# final_2_connectors.net
KiCad netlist of a schematic drawn in EAGLE
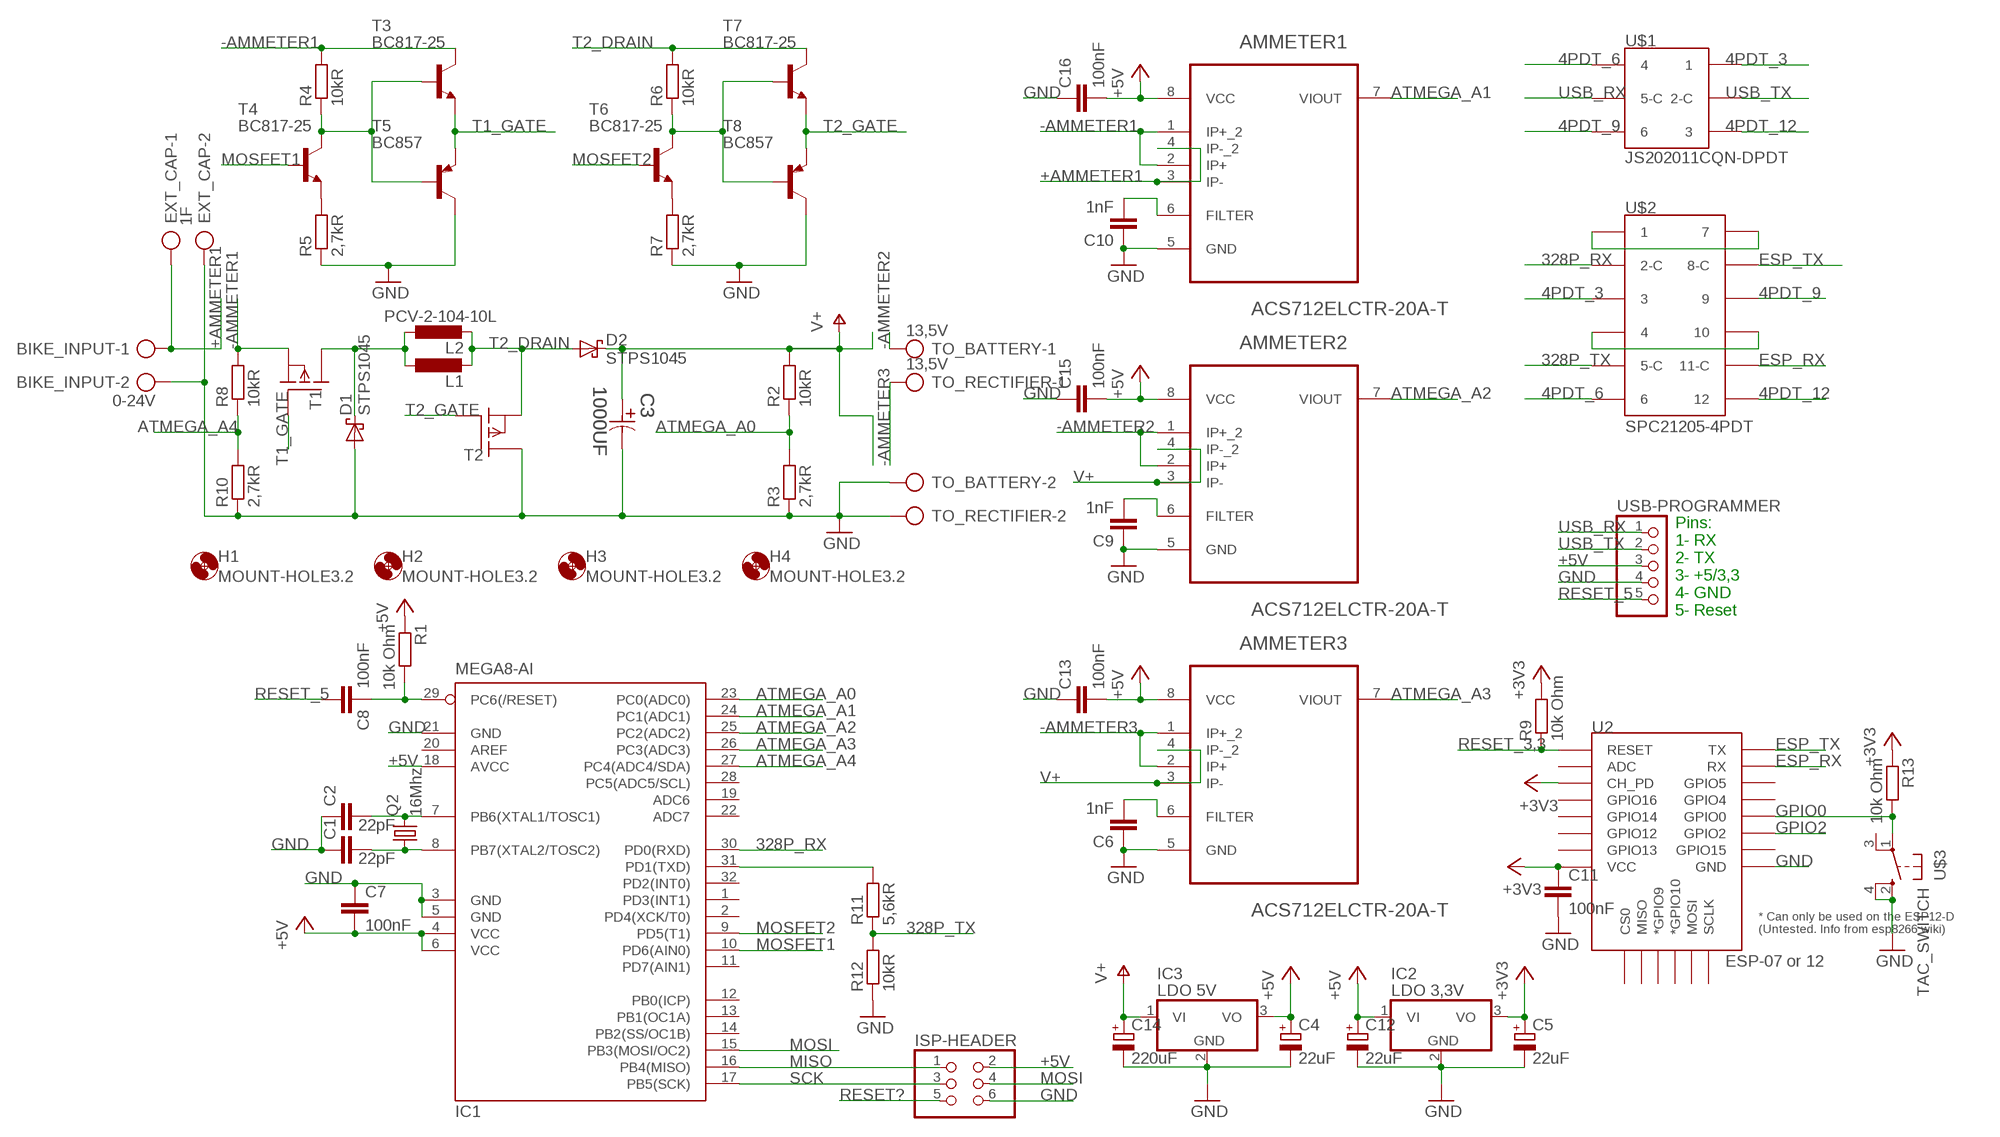
[diagram p0: schematic, sheet 1]

(export (version "E")
  (design (tool "Eeschema 10.0.6"))
  (components
    (comp (ref "AMMETER1")
      (value "ACS712ELCTR-20A-T")
      (footprint "eagle-import:SOIC127P600X175-8N")
      (libsource (lib "eagle-import") (part "ACS712ELCTR-20A-T"))
    )
    (comp (ref "AMMETER2")
      (value "ACS712ELCTR-20A-T")
      (footprint "eagle-import:SOIC127P600X175-8N")
      (libsource (lib "eagle-import") (part "ACS712ELCTR-20A-T"))
    )
    (comp (ref "AMMETER3")
      (value "ACS712ELCTR-20A-T")
      (footprint "eagle-import:SOIC127P600X175-8N")
      (libsource (lib "eagle-import") (part "ACS712ELCTR-20A-T"))
    )
    (comp (ref "BIKE_INPUT")
      (value "0-24V")
      (footprint "eagle-import:AK500_2")
      (libsource (lib "eagle-import") (part "AK500/2"))
    )
    (comp (ref "C1")
      (value "22pF")
      (footprint "eagle-import:C0805")
      (libsource (lib "eagle-import") (part "C-EUC0805"))
    )
    (comp (ref "C2")
      (value "22pF")
      (footprint "eagle-import:C0805")
      (libsource (lib "eagle-import") (part "C-EUC0805"))
    )
    (comp (ref "C3")
      (value "1000UF")
      (footprint "eagle-import:CAPAE1700X1700N")
      (fields (field (name "MPN") "EEVFK1H102M") (field (name "TOLERANCE") "±20 %"))
      (libsource (lib "eagle-import") (part "EEV--CASE-J16FK1H102M"))
    )
    (comp (ref "C4")
      (value "22uF")
      (footprint "eagle-import:153CLV-0505")
      (libsource (lib "eagle-import") (part "CPOL-EU153CLV-0505"))
    )
    (comp (ref "C5")
      (value "22uF")
      (footprint "eagle-import:153CLV-0505")
      (libsource (lib "eagle-import") (part "CPOL-EU153CLV-0505"))
    )
    (comp (ref "C6")
      (value "1nF")
      (footprint "eagle-import:C0805")
      (libsource (lib "eagle-import") (part "C-EUC0805"))
    )
    (comp (ref "C7")
      (value "100nF")
      (footprint "eagle-import:C0805")
      (libsource (lib "eagle-import") (part "C-EUC0805"))
    )
    (comp (ref "C8")
      (value "100nF")
      (footprint "eagle-import:C0805")
      (libsource (lib "eagle-import") (part "C-EUC0805"))
    )
    (comp (ref "C9")
      (value "1nF")
      (footprint "eagle-import:C0805")
      (libsource (lib "eagle-import") (part "C-EUC0805"))
    )
    (comp (ref "C10")
      (value "1nF")
      (footprint "eagle-import:C0805")
      (libsource (lib "eagle-import") (part "C-EUC0805"))
    )
    (comp (ref "C11")
      (value "100nF")
      (footprint "eagle-import:C0805")
      (libsource (lib "eagle-import") (part "C-EUC0805"))
    )
    (comp (ref "C12")
      (value "22uF")
      (footprint "eagle-import:153CLV-0505")
      (libsource (lib "eagle-import") (part "CPOL-EU153CLV-0505"))
    )
    (comp (ref "C13")
      (value "100nF")
      (footprint "eagle-import:C0805")
      (libsource (lib "eagle-import") (part "C-EUC0805"))
    )
    (comp (ref "C14")
      (value "220uF")
      (footprint "eagle-import:153CLV-0807")
      (libsource (lib "eagle-import") (part "CPOL-EU153CLV-0807"))
    )
    (comp (ref "C15")
      (value "100nF")
      (footprint "eagle-import:C0805")
      (libsource (lib "eagle-import") (part "C-EUC0805"))
    )
    (comp (ref "C16")
      (value "100nF")
      (footprint "eagle-import:C0805")
      (libsource (lib "eagle-import") (part "C-EUC0805"))
    )
    (comp (ref "D1")
      (value "STPS1045")
      (footprint "eagle-import:TO220AC")
      (libsource (lib "eagle-import") (part "STPS1045"))
    )
    (comp (ref "D2")
      (value "STPS1045")
      (footprint "eagle-import:TO220AC")
      (libsource (lib "eagle-import") (part "STPS1045"))
    )
    (comp (ref "EXT_CAP")
      (value "1F")
      (footprint "eagle-import:AK500_2")
      (libsource (lib "eagle-import") (part "AK500/2"))
    )
    (comp (ref "H1")
      (value "MOUNT-HOLE3.2")
      (footprint "eagle-import:3,2")
      (libsource (lib "eagle-import") (part "MOUNT-HOLE3.2"))
    )
    (comp (ref "H2")
      (value "MOUNT-HOLE3.2")
      (footprint "eagle-import:3,2")
      (libsource (lib "eagle-import") (part "MOUNT-HOLE3.2"))
    )
    (comp (ref "H3")
      (value "MOUNT-HOLE3.2")
      (footprint "eagle-import:3,2")
      (libsource (lib "eagle-import") (part "MOUNT-HOLE3.2"))
    )
    (comp (ref "H4")
      (value "MOUNT-HOLE3.2")
      (footprint "eagle-import:3,2")
      (libsource (lib "eagle-import") (part "MOUNT-HOLE3.2"))
    )
    (comp (ref "IC1")
      (value "MEGA8-AI")
      (footprint "eagle-import:TQFP32-08")
      (fields (field (name "MPN") "ATMEGA8-16AU"))
      (libsource (lib "eagle-import") (part "MEGA8-AI"))
    )
    (comp (ref "IC2")
      (value "LDO 3,3V")
      (footprint "eagle-import:SOT223")
      (libsource (lib "eagle-import") (part "MCP1703DB"))
    )
    (comp (ref "IC3")
      (value "LDO 5V")
      (footprint "eagle-import:SOT223")
      (libsource (lib "eagle-import") (part "MCP1703DB"))
    )
    (comp (ref "ISP-HEADER")
      (value "PINHD-2X3")
      (footprint "eagle-import:2X03")
      (libsource (lib "eagle-import") (part "PINHD-2X3"))
    )
    (comp (ref "L1")
      (value "PCV-2-104-10L")
      (footprint "eagle-import:TJ5-U2")
      (libsource (lib "eagle-import") (part "PCV-2-104-10L"))
    )
    (comp (ref "L2")
      (value "PCV-2-104-10L")
      (footprint "eagle-import:TJ5-U2")
      (libsource (lib "eagle-import") (part "PCV-2-104-10L"))
    )
    (comp (ref "Q2")
      (value "16Mhz")
      (footprint "eagle-import:HC49UP")
      (libsource (lib "eagle-import") (part "CRYSTALHC49UP"))
    )
    (comp (ref "R1")
      (value "10k Ohm")
      (footprint "eagle-import:M0805")
      (libsource (lib "eagle-import") (part "R-EU_M0805"))
    )
    (comp (ref "R2")
      (value "10kR")
      (footprint "eagle-import:M0805")
      (libsource (lib "eagle-import") (part "R-EU_M0805"))
    )
    (comp (ref "R3")
      (value "2,7kR")
      (footprint "eagle-import:M0805")
      (libsource (lib "eagle-import") (part "R-EU_M0805"))
    )
    (comp (ref "R4")
      (value "10kR")
      (footprint "eagle-import:M0805")
      (libsource (lib "eagle-import") (part "R-EU_M0805"))
    )
    (comp (ref "R5")
      (value "2,7kR")
      (footprint "eagle-import:M0805")
      (libsource (lib "eagle-import") (part "R-EU_M0805"))
    )
    (comp (ref "R6")
      (value "10kR")
      (footprint "eagle-import:M0805")
      (libsource (lib "eagle-import") (part "R-EU_M0805"))
    )
    (comp (ref "R7")
      (value "2,7kR")
      (footprint "eagle-import:M0805")
      (libsource (lib "eagle-import") (part "R-EU_M0805"))
    )
    (comp (ref "R8")
      (value "10kR")
      (footprint "eagle-import:M0805")
      (libsource (lib "eagle-import") (part "R-EU_M0805"))
    )
    (comp (ref "R9")
      (value "10k Ohm")
      (footprint "eagle-import:M0805")
      (libsource (lib "eagle-import") (part "R-EU_M0805"))
    )
    (comp (ref "R10")
      (value "2,7kR")
      (footprint "eagle-import:M0805")
      (libsource (lib "eagle-import") (part "R-EU_M0805"))
    )
    (comp (ref "R11")
      (value "5,6kR")
      (footprint "eagle-import:M0805")
      (libsource (lib "eagle-import") (part "R-EU_M0805"))
    )
    (comp (ref "R12")
      (value "10kR")
      (footprint "eagle-import:M0805")
      (libsource (lib "eagle-import") (part "R-EU_M0805"))
    )
    (comp (ref "R13")
      (value "10k Ohm")
      (footprint "eagle-import:M0805")
      (libsource (lib "eagle-import") (part "R-EU_M0805"))
    )
    (comp (ref "T1")
      (value "SUP65P06-20")
      (footprint "eagle-import:TO220")
      (libsource (lib "eagle-import") (part "SUP65P06-20"))
    )
    (comp (ref "T2")
      (value "SUP65P06-20")
      (footprint "eagle-import:TO220")
      (libsource (lib "eagle-import") (part "SUP65P06-20"))
    )
    (comp (ref "T3")
      (value "BC817-25")
      (footprint "eagle-import:SOT23-BEC")
      (libsource (lib "eagle-import") (part "-NPN-SOT23-BECBC817-25"))
    )
    (comp (ref "T4")
      (value "BC817-25")
      (footprint "eagle-import:SOT23-BEC")
      (libsource (lib "eagle-import") (part "-NPN-SOT23-BECBC817-25"))
    )
    (comp (ref "T5")
      (value "BC857")
      (footprint "eagle-import:SOT23-BEC")
      (libsource (lib "eagle-import") (part "-PNP-SOT23-BECBC857ALT1"))
    )
    (comp (ref "T6")
      (value "BC817-25")
      (footprint "eagle-import:SOT23-BEC")
      (libsource (lib "eagle-import") (part "-NPN-SOT23-BECBC817-25"))
    )
    (comp (ref "T7")
      (value "BC817-25")
      (footprint "eagle-import:SOT23-BEC")
      (libsource (lib "eagle-import") (part "-NPN-SOT23-BECBC817-25"))
    )
    (comp (ref "T8")
      (value "BC857")
      (footprint "eagle-import:SOT23-BEC")
      (libsource (lib "eagle-import") (part "-PNP-SOT23-BECBC857ALT1"))
    )
    (comp (ref "TO_BATTERY")
      (value "13,5V")
      (footprint "eagle-import:AK500_2")
      (libsource (lib "eagle-import") (part "AK500/2"))
    )
    (comp (ref "TO_RECTIFIER")
      (value "13,5V")
      (footprint "eagle-import:AK500_2")
      (libsource (lib "eagle-import") (part "AK500/2"))
    )
    (comp (ref "U$1")
      (value "JS202011CQN-DPDT")
      (footprint "eagle-import:2X3_SWITCH")
      (libsource (lib "eagle-import") (part "JS202011CQN-DPDT"))
    )
    (comp (ref "U$2")
      (value "SPC21205-4PDT")
      (footprint "eagle-import:2X6_SWITCH")
      (libsource (lib "eagle-import") (part "SPC21205-4PDT"))
    )
    (comp (ref "U$3")
      (value "TAC_SWITCH")
      (footprint "eagle-import:TL1105SP")
      (libsource (lib "eagle-import") (part "TAC_SWITCH"))
    )
    (comp (ref "U2")
      (value "ESP-07 or 12")
      (footprint "eagle-import:ESP12E-SMD")
      (libsource (lib "eagle-import") (part "ESP12ESMD"))
    )
    (comp (ref "USB-PROGRAMMER")
      (value "PINHD-1X5")
      (footprint "eagle-import:1X05")
      (libsource (lib "eagle-import") (part "PINHD-1X5"))
    )
  )
  (nets
    (net (code "1") (name "+3V3") (class "Default")
      (node (ref "C11") (pin "1") (pinfunction "1_1") (pintype "passive"))
      (node (ref "C5") (pin "+") (pinfunction "+_+") (pintype "passive"))
      (node (ref "IC2") (pin "3") (pinfunction "VO_3") (pintype "passive"))
      (node (ref "R13") (pin "1") (pinfunction "1_1") (pintype "passive"))
      (node (ref "R9") (pin "2") (pinfunction "2_2") (pintype "passive"))
      (node (ref "U2") (pin "CH_PD") (pinfunction "CH_PD_CH_PD") (pintype "bidirectional"))
      (node (ref "U2") (pin "VCC") (pinfunction "VCC_VCC") (pintype "bidirectional"))
    )
    (net (code "2") (name "+5V") (class "Default")
      (node (ref "AMMETER1") (pin "8") (pinfunction "VCC_8") (pintype "power_in"))
      (node (ref "AMMETER2") (pin "8") (pinfunction "VCC_8") (pintype "power_in"))
      (node (ref "AMMETER3") (pin "8") (pinfunction "VCC_8") (pintype "power_in"))
      (node (ref "C12") (pin "+") (pinfunction "+_+") (pintype "passive"))
      (node (ref "C13") (pin "2") (pinfunction "2_2") (pintype "passive"))
      (node (ref "C15") (pin "2") (pinfunction "2_2") (pintype "passive"))
      (node (ref "C16") (pin "2") (pinfunction "2_2") (pintype "passive"))
      (node (ref "C4") (pin "+") (pinfunction "+_+") (pintype "passive"))
      (node (ref "C7") (pin "2") (pinfunction "2_2") (pintype "passive"))
      (node (ref "IC1") (pin "18") (pinfunction "AVCC_18") (pintype "power_in"))
      (node (ref "IC1") (pin "4") (pinfunction "VCC_4") (pintype "power_in"))
      (node (ref "IC1") (pin "6") (pinfunction "VCC_6") (pintype "power_in"))
      (node (ref "IC2") (pin "1") (pinfunction "VI_1") (pintype "input"))
      (node (ref "IC3") (pin "3") (pinfunction "VO_3") (pintype "passive"))
      (node (ref "ISP-HEADER") (pin "2") (pinfunction "2_2") (pintype "passive"))
      (node (ref "R1") (pin "1") (pinfunction "1_1") (pintype "passive"))
      (node (ref "USB-PROGRAMMER") (pin "3") (pinfunction "3_3") (pintype "passive"))
    )
    (net (code "3") (name "/+AMMETER1") (class "Default")
      (node (ref "AMMETER1") (pin "3") (pinfunction "IP-_3") (pintype "input"))
      (node (ref "AMMETER1") (pin "4") (pinfunction "IP-_2_4") (pintype "input"))
      (node (ref "BIKE_INPUT") (pin "1") (pinfunction "KL_1") (pintype "passive"))
      (node (ref "EXT_CAP") (pin "1") (pinfunction "KL_1") (pintype "passive"))
    )
    (net (code "4") (name "/-AMMETER1") (class "Default")
      (node (ref "AMMETER1") (pin "1") (pinfunction "IP+_2_1") (pintype "input"))
      (node (ref "AMMETER1") (pin "2") (pinfunction "IP+_2") (pintype "input"))
      (node (ref "R4") (pin "2") (pinfunction "2_2") (pintype "passive"))
      (node (ref "R8") (pin "2") (pinfunction "2_2") (pintype "passive"))
      (node (ref "T1") (pin "3") (pinfunction "S_3") (pintype "passive"))
      (node (ref "T3") (pin "C") (pinfunction "C_C") (pintype "passive"))
    )
    (net (code "5") (name "/-AMMETER2") (class "Default")
      (node (ref "AMMETER2") (pin "1") (pinfunction "IP+_2_1") (pintype "input"))
      (node (ref "AMMETER2") (pin "2") (pinfunction "IP+_2") (pintype "input"))
      (node (ref "TO_BATTERY") (pin "1") (pinfunction "KL_1") (pintype "passive"))
    )
    (net (code "6") (name "/-AMMETER3") (class "Default")
      (node (ref "AMMETER3") (pin "1") (pinfunction "IP+_2_1") (pintype "input"))
      (node (ref "AMMETER3") (pin "2") (pinfunction "IP+_2") (pintype "input"))
      (node (ref "TO_RECTIFIER") (pin "1") (pinfunction "KL_1") (pintype "passive"))
    )
    (net (code "7") (name "/4PDT_3") (class "Default")
      (node (ref "U$1") (pin "1") (pinfunction "1_1") (pintype "bidirectional"))
      (node (ref "U$2") (pin "3") (pinfunction "3_3") (pintype "bidirectional"))
    )
    (net (code "8") (name "/4PDT_6") (class "Default")
      (node (ref "U$1") (pin "4") (pinfunction "4_4") (pintype "bidirectional"))
      (node (ref "U$2") (pin "6") (pinfunction "6_6") (pintype "bidirectional"))
    )
    (net (code "9") (name "/4PDT_9") (class "Default")
      (node (ref "U$1") (pin "6") (pinfunction "6_6") (pintype "bidirectional"))
      (node (ref "U$2") (pin "9") (pinfunction "9_9") (pintype "bidirectional"))
    )
    (net (code "10") (name "/4PDT_12") (class "Default")
      (node (ref "U$1") (pin "3") (pinfunction "3_3") (pintype "bidirectional"))
      (node (ref "U$2") (pin "12") (pinfunction "12_12") (pintype "bidirectional"))
    )
    (net (code "11") (name "/328P_RX") (class "Default")
      (node (ref "IC1") (pin "30") (pinfunction "PD0(RXD)_30") (pintype "bidirectional"))
      (node (ref "U$2") (pin "2-C") (pinfunction "2-C_2-C") (pintype "bidirectional"))
    )
    (net (code "12") (name "/328P_TX") (class "Default")
      (node (ref "R11") (pin "1") (pinfunction "1_1") (pintype "passive"))
      (node (ref "R12") (pin "2") (pinfunction "2_2") (pintype "passive"))
      (node (ref "U$2") (pin "5-C") (pinfunction "5-C_5-C") (pintype "bidirectional"))
    )
    (net (code "13") (name "/ATMEGA_A0") (class "Default")
      (node (ref "IC1") (pin "23") (pinfunction "PC0(ADC0)_23") (pintype "bidirectional"))
      (node (ref "R2") (pin "1") (pinfunction "1_1") (pintype "passive"))
      (node (ref "R3") (pin "2") (pinfunction "2_2") (pintype "passive"))
    )
    (net (code "14") (name "/ATMEGA_A1") (class "Default")
      (node (ref "AMMETER1") (pin "7") (pinfunction "VIOUT_7") (pintype "output"))
      (node (ref "IC1") (pin "24") (pinfunction "PC1(ADC1)_24") (pintype "bidirectional"))
    )
    (net (code "15") (name "/ATMEGA_A2") (class "Default")
      (node (ref "AMMETER2") (pin "7") (pinfunction "VIOUT_7") (pintype "output"))
      (node (ref "IC1") (pin "25") (pinfunction "PC2(ADC2)_25") (pintype "bidirectional"))
    )
    (net (code "16") (name "/ATMEGA_A3") (class "Default")
      (node (ref "AMMETER3") (pin "7") (pinfunction "VIOUT_7") (pintype "output"))
      (node (ref "IC1") (pin "26") (pinfunction "PC3(ADC3)_26") (pintype "bidirectional"))
    )
    (net (code "17") (name "/ATMEGA_A4") (class "Default")
      (node (ref "IC1") (pin "27") (pinfunction "PC4(ADC4/SDA)_27") (pintype "bidirectional"))
      (node (ref "R10") (pin "2") (pinfunction "2_2") (pintype "passive"))
      (node (ref "R8") (pin "1") (pinfunction "1_1") (pintype "passive"))
    )
    (net (code "18") (name "/ESP_RX") (class "Default")
      (node (ref "U$2") (pin "11-C") (pinfunction "11-C_11-C") (pintype "bidirectional"))
      (node (ref "U2") (pin "RXD0") (pinfunction "RX_RXD0") (pintype "bidirectional"))
    )
    (net (code "19") (name "/ESP_TX") (class "Default")
      (node (ref "U$2") (pin "8-C") (pinfunction "8-C_8-C") (pintype "bidirectional"))
      (node (ref "U2") (pin "TXD0") (pinfunction "TX_TXD0") (pintype "bidirectional"))
    )
    (net (code "20") (name "/GPIO0") (class "Default")
      (node (ref "R13") (pin "2") (pinfunction "2_2") (pintype "passive"))
      (node (ref "U$3") (pin "1") (pinfunction "P_1") (pintype "passive"))
      (node (ref "U2") (pin "GPIO0") (pinfunction "GPIO0_GPIO0") (pintype "bidirectional"))
    )
    (net (code "21") (name "/GPIO2") (class "Default")
      (node (ref "U2") (pin "GPIO2") (pinfunction "GPIO2_GPIO2") (pintype "bidirectional"))
    )
    (net (code "22") (name "/MISO") (class "Default")
      (node (ref "IC1") (pin "16") (pinfunction "PB4(MISO)_16") (pintype "bidirectional"))
      (node (ref "ISP-HEADER") (pin "1") (pinfunction "1_1") (pintype "passive"))
    )
    (net (code "23") (name "/MOSFET1") (class "Default")
      (node (ref "IC1") (pin "10") (pinfunction "PD6(AIN0)_10") (pintype "bidirectional"))
      (node (ref "T4") (pin "B") (pinfunction "B_B") (pintype "passive"))
    )
    (net (code "24") (name "/MOSFET2") (class "Default")
      (node (ref "IC1") (pin "9") (pinfunction "PD5(T1)_9") (pintype "bidirectional"))
      (node (ref "T6") (pin "B") (pinfunction "B_B") (pintype "passive"))
    )
    (net (code "25") (name "/MOSI") (class "Default")
      (node (ref "IC1") (pin "15") (pinfunction "PB3(MOSI/OC2)_15") (pintype "bidirectional"))
      (node (ref "ISP-HEADER") (pin "4") (pinfunction "4_4") (pintype "passive"))
    )
    (net (code "26") (name "/RESET?") (class "Default")
      (node (ref "ISP-HEADER") (pin "5") (pinfunction "5_5") (pintype "passive"))
    )
    (net (code "27") (name "/RESET_3,3") (class "Default")
      (node (ref "R9") (pin "1") (pinfunction "1_1") (pintype "passive"))
      (node (ref "U2") (pin "RESET") (pinfunction "RESET_RESET") (pintype "bidirectional"))
    )
    (net (code "28") (name "/RESET_5") (class "Default")
      (node (ref "C8") (pin "2") (pinfunction "2_2") (pintype "passive"))
      (node (ref "USB-PROGRAMMER") (pin "5") (pinfunction "5_5") (pintype "passive"))
    )
    (net (code "29") (name "/SCK") (class "Default")
      (node (ref "IC1") (pin "17") (pinfunction "PB5(SCK)_17") (pintype "bidirectional"))
      (node (ref "ISP-HEADER") (pin "3") (pinfunction "3_3") (pintype "passive"))
    )
    (net (code "30") (name "/T1_GATE") (class "Default")
      (node (ref "T1") (pin "1") (pinfunction "G_1") (pintype "passive"))
      (node (ref "T3") (pin "E") (pinfunction "E_E") (pintype "passive"))
      (node (ref "T5") (pin "E") (pinfunction "E_E") (pintype "passive"))
    )
    (net (code "31") (name "/T2_DRAIN") (class "Default")
      (node (ref "D2") (pin "A") (pinfunction "A_A") (pintype "passive"))
      (node (ref "L1") (pin "2") (pinfunction "2_2") (pintype "passive"))
      (node (ref "L2") (pin "2") (pinfunction "2_2") (pintype "passive"))
      (node (ref "R6") (pin "2") (pinfunction "2_2") (pintype "passive"))
      (node (ref "T2") (pin "3") (pinfunction "S_3") (pintype "passive"))
      (node (ref "T7") (pin "C") (pinfunction "C_C") (pintype "passive"))
    )
    (net (code "32") (name "/T2_GATE") (class "Default")
      (node (ref "T2") (pin "1") (pinfunction "G_1") (pintype "passive"))
      (node (ref "T7") (pin "E") (pinfunction "E_E") (pintype "passive"))
      (node (ref "T8") (pin "E") (pinfunction "E_E") (pintype "passive"))
    )
    (net (code "33") (name "/USB_RX") (class "Default")
      (node (ref "U$1") (pin "5-C") (pinfunction "5-C_5-C") (pintype "bidirectional"))
      (node (ref "USB-PROGRAMMER") (pin "1") (pinfunction "1_1") (pintype "passive"))
    )
    (net (code "34") (name "/USB_TX") (class "Default")
      (node (ref "U$1") (pin "2-C") (pinfunction "2-C_2-C") (pintype "bidirectional"))
      (node (ref "USB-PROGRAMMER") (pin "2") (pinfunction "2_2") (pintype "passive"))
    )
    (net (code "35") (name "GND") (class "Default")
      (node (ref "AMMETER1") (pin "5") (pinfunction "GND_5") (pintype "passive"))
      (node (ref "AMMETER2") (pin "5") (pinfunction "GND_5") (pintype "passive"))
      (node (ref "AMMETER3") (pin "5") (pinfunction "GND_5") (pintype "passive"))
      (node (ref "BIKE_INPUT") (pin "2") (pinfunction "KL_2") (pintype "passive"))
      (node (ref "C1") (pin "1") (pinfunction "1_1") (pintype "passive"))
      (node (ref "C10") (pin "1") (pinfunction "1_1") (pintype "passive"))
      (node (ref "C11") (pin "2") (pinfunction "2_2") (pintype "passive"))
      (node (ref "C12") (pin "-") (pinfunction "-_-") (pintype "passive"))
      (node (ref "C13") (pin "1") (pinfunction "1_1") (pintype "passive"))
      (node (ref "C14") (pin "-") (pinfunction "-_-") (pintype "passive"))
      (node (ref "C15") (pin "1") (pinfunction "1_1") (pintype "passive"))
      (node (ref "C16") (pin "1") (pinfunction "1_1") (pintype "passive"))
      (node (ref "C2") (pin "1") (pinfunction "1_1") (pintype "passive"))
      (node (ref "C3") (pin "2") (pinfunction "2_2") (pintype "passive"))
      (node (ref "C4") (pin "-") (pinfunction "-_-") (pintype "passive"))
      (node (ref "C5") (pin "-") (pinfunction "-_-") (pintype "passive"))
      (node (ref "C6") (pin "1") (pinfunction "1_1") (pintype "passive"))
      (node (ref "C7") (pin "1") (pinfunction "1_1") (pintype "passive"))
      (node (ref "C9") (pin "1") (pinfunction "1_1") (pintype "passive"))
      (node (ref "D1") (pin "A") (pinfunction "A_A") (pintype "passive"))
      (node (ref "EXT_CAP") (pin "2") (pinfunction "KL_2") (pintype "passive"))
      (node (ref "IC1") (pin "21") (pinfunction "GND_21") (pintype "power_in"))
      (node (ref "IC1") (pin "3") (pinfunction "GND_3") (pintype "power_in"))
      (node (ref "IC1") (pin "5") (pinfunction "GND_5") (pintype "power_in"))
      (node (ref "IC2") (pin "2") (pinfunction "GND_2") (pintype "passive"))
      (node (ref "IC3") (pin "2") (pinfunction "GND_2") (pintype "passive"))
      (node (ref "ISP-HEADER") (pin "6") (pinfunction "6_6") (pintype "passive"))
      (node (ref "R10") (pin "1") (pinfunction "1_1") (pintype "passive"))
      (node (ref "R12") (pin "1") (pinfunction "1_1") (pintype "passive"))
      (node (ref "R3") (pin "1") (pinfunction "1_1") (pintype "passive"))
      (node (ref "R5") (pin "1") (pinfunction "1_1") (pintype "passive"))
      (node (ref "R7") (pin "1") (pinfunction "1_1") (pintype "passive"))
      (node (ref "T2") (pin "2") (pinfunction "D_2") (pintype "passive"))
      (node (ref "T5") (pin "C") (pinfunction "C_C") (pintype "passive"))
      (node (ref "T8") (pin "C") (pinfunction "C_C") (pintype "passive"))
      (node (ref "TO_BATTERY") (pin "2") (pinfunction "KL_2") (pintype "passive"))
      (node (ref "TO_RECTIFIER") (pin "2") (pinfunction "KL_2") (pintype "passive"))
      (node (ref "U$3") (pin "2") (pinfunction "S_2") (pintype "passive"))
      (node (ref "U$3") (pin "4") (pinfunction "S1_4") (pintype "passive"))
      (node (ref "U2") (pin "GND") (pinfunction "GND_GND") (pintype "bidirectional"))
      (node (ref "USB-PROGRAMMER") (pin "4") (pinfunction "4_4") (pintype "passive"))
    )
    (net (code "36") (name "Net-(AMMETER1-FILTER)") (class "Default")
      (node (ref "AMMETER1") (pin "6") (pinfunction "FILTER_6") (pintype "input"))
      (node (ref "C10") (pin "2") (pinfunction "2_2") (pintype "passive"))
    )
    (net (code "37") (name "Net-(AMMETER2-FILTER)") (class "Default")
      (node (ref "AMMETER2") (pin "6") (pinfunction "FILTER_6") (pintype "input"))
      (node (ref "C9") (pin "2") (pinfunction "2_2") (pintype "passive"))
    )
    (net (code "38") (name "Net-(AMMETER3-FILTER)") (class "Default")
      (node (ref "AMMETER3") (pin "6") (pinfunction "FILTER_6") (pintype "input"))
      (node (ref "C6") (pin "2") (pinfunction "2_2") (pintype "passive"))
    )
    (net (code "39") (name "Net-(IC1-PB6(XTAL1{slash}TOSC1))") (class "Default")
      (node (ref "C2") (pin "2") (pinfunction "2_2") (pintype "passive"))
      (node (ref "IC1") (pin "7") (pinfunction "PB6(XTAL1/TOSC1)_7") (pintype "bidirectional"))
      (node (ref "Q2") (pin "2") (pinfunction "2_2") (pintype "passive"))
    )
    (net (code "40") (name "Net-(IC1-PB7(XTAL2{slash}TOSC2))") (class "Default")
      (node (ref "C1") (pin "2") (pinfunction "2_2") (pintype "passive"))
      (node (ref "IC1") (pin "8") (pinfunction "PB7(XTAL2/TOSC2)_8") (pintype "bidirectional"))
      (node (ref "Q2") (pin "1") (pinfunction "1_1") (pintype "passive"))
    )
    (net (code "41") (name "Net-(IC1-PC6({slash}RESET))") (class "Default")
      (node (ref "C8") (pin "1") (pinfunction "1_1") (pintype "passive"))
      (node (ref "IC1") (pin "29") (pinfunction "PC6(/RESET)_29") (pintype "bidirectional"))
      (node (ref "R1") (pin "2") (pinfunction "2_2") (pintype "passive"))
    )
    (net (code "42") (name "Net-(IC1-PD1(TXD))") (class "Default")
      (node (ref "IC1") (pin "31") (pinfunction "PD1(TXD)_31") (pintype "bidirectional"))
      (node (ref "R11") (pin "2") (pinfunction "2_2") (pintype "passive"))
    )
    (net (code "43") (name "Net-(R4-Pad1)") (class "Default")
      (node (ref "R4") (pin "1") (pinfunction "1_1") (pintype "passive"))
      (node (ref "T3") (pin "B") (pinfunction "B_B") (pintype "passive"))
      (node (ref "T4") (pin "C") (pinfunction "C_C") (pintype "passive"))
      (node (ref "T5") (pin "B") (pinfunction "B_B") (pintype "passive"))
    )
    (net (code "44") (name "Net-(R5-Pad2)") (class "Default")
      (node (ref "R5") (pin "2") (pinfunction "2_2") (pintype "passive"))
      (node (ref "T4") (pin "E") (pinfunction "E_E") (pintype "passive"))
    )
    (net (code "45") (name "Net-(R6-Pad1)") (class "Default")
      (node (ref "R6") (pin "1") (pinfunction "1_1") (pintype "passive"))
      (node (ref "T6") (pin "C") (pinfunction "C_C") (pintype "passive"))
      (node (ref "T7") (pin "B") (pinfunction "B_B") (pintype "passive"))
      (node (ref "T8") (pin "B") (pinfunction "B_B") (pintype "passive"))
    )
    (net (code "46") (name "Net-(R7-Pad2)") (class "Default")
      (node (ref "R7") (pin "2") (pinfunction "2_2") (pintype "passive"))
      (node (ref "T6") (pin "E") (pinfunction "E_E") (pintype "passive"))
    )
    (net (code "47") (name "Net-(T1-D)") (class "Default")
      (node (ref "D1") (pin "C") (pinfunction "C_C") (pintype "passive"))
      (node (ref "L1") (pin "1") (pinfunction "1_1") (pintype "passive"))
      (node (ref "L2") (pin "1") (pinfunction "1_1") (pintype "passive"))
      (node (ref "T1") (pin "2") (pinfunction "D_2") (pintype "passive"))
    )
    (net (code "48") (name "Net-(U$2-Pad1)") (class "Default")
      (node (ref "U$2") (pin "1") (pinfunction "1_1") (pintype "bidirectional"))
      (node (ref "U$2") (pin "7") (pinfunction "7_7") (pintype "bidirectional"))
    )
    (net (code "49") (name "Net-(U$2-Pad10)") (class "Default")
      (node (ref "U$2") (pin "10") (pinfunction "10_10") (pintype "bidirectional"))
      (node (ref "U$2") (pin "4") (pinfunction "4_4") (pintype "bidirectional"))
    )
    (net (code "50") (name "V+") (class "Default")
      (node (ref "AMMETER2") (pin "3") (pinfunction "IP-_3") (pintype "input"))
      (node (ref "AMMETER2") (pin "4") (pinfunction "IP-_2_4") (pintype "input"))
      (node (ref "AMMETER3") (pin "3") (pinfunction "IP-_3") (pintype "input"))
      (node (ref "AMMETER3") (pin "4") (pinfunction "IP-_2_4") (pintype "input"))
      (node (ref "C14") (pin "+") (pinfunction "+_+") (pintype "passive"))
      (node (ref "C3") (pin "1") (pinfunction "1_1") (pintype "passive"))
      (node (ref "D2") (pin "C") (pinfunction "C_C") (pintype "passive"))
      (node (ref "IC3") (pin "1") (pinfunction "VI_1") (pintype "input"))
      (node (ref "R2") (pin "2") (pinfunction "2_2") (pintype "passive"))
    )
    (net (code "51") (name "unconnected-(IC1-ADC6-Pad19)") (class "Default")
      (node (ref "IC1") (pin "19") (pinfunction "ADC6_19") (pintype "bidirectional"))
    )
    (net (code "52") (name "unconnected-(IC1-ADC7-Pad22)") (class "Default")
      (node (ref "IC1") (pin "22") (pinfunction "ADC7_22") (pintype "bidirectional"))
    )
    (net (code "53") (name "unconnected-(IC1-AREF-Pad20)") (class "Default")
      (node (ref "IC1") (pin "20") (pinfunction "AREF_20") (pintype "passive"))
    )
    (net (code "54") (name "unconnected-(IC1-PB0(ICP)-Pad12)") (class "Default")
      (node (ref "IC1") (pin "12") (pinfunction "PB0(ICP)_12") (pintype "bidirectional"))
    )
    (net (code "55") (name "unconnected-(IC1-PB1(OC1A)-Pad13)") (class "Default")
      (node (ref "IC1") (pin "13") (pinfunction "PB1(OC1A)_13") (pintype "bidirectional"))
    )
    (net (code "56") (name "unconnected-(IC1-PB2(SS{slash}OC1B)-Pad14)") (class "Default")
      (node (ref "IC1") (pin "14") (pinfunction "PB2(SS/OC1B)_14") (pintype "bidirectional"))
    )
    (net (code "57") (name "unconnected-(IC1-PC5(ADC5{slash}SCL)-Pad28)") (class "Default")
      (node (ref "IC1") (pin "28") (pinfunction "PC5(ADC5/SCL)_28") (pintype "bidirectional"))
    )
    (net (code "58") (name "unconnected-(IC1-PD2(INT0)-Pad32)") (class "Default")
      (node (ref "IC1") (pin "32") (pinfunction "PD2(INT0)_32") (pintype "bidirectional"))
    )
    (net (code "59") (name "unconnected-(IC1-PD3(INT1)-Pad1)") (class "Default")
      (node (ref "IC1") (pin "1") (pinfunction "PD3(INT1)_1") (pintype "bidirectional"))
    )
    (net (code "60") (name "unconnected-(IC1-PD4(XCK{slash}T0)-Pad2)") (class "Default")
      (node (ref "IC1") (pin "2") (pinfunction "PD4(XCK/T0)_2") (pintype "bidirectional"))
    )
    (net (code "61") (name "unconnected-(IC1-PD7(AIN1)-Pad11)") (class "Default")
      (node (ref "IC1") (pin "11") (pinfunction "PD7(AIN1)_11") (pintype "bidirectional"))
    )
    (net (code "62") (name "unconnected-(U$3-P1-Pad3)") (class "Default")
      (node (ref "U$3") (pin "3") (pinfunction "P1_3") (pintype "passive"))
    )
    (net (code "63") (name "unconnected-(U2-*GPIO9-PadGPIO9)") (class "Default")
      (node (ref "U2") (pin "GPIO9") (pinfunction "*GPIO9_GPIO9") (pintype "bidirectional"))
    )
    (net (code "64") (name "unconnected-(U2-*GPIO10-PadGPIO10)") (class "Default")
      (node (ref "U2") (pin "GPIO10") (pinfunction "*GPIO10_GPIO10") (pintype "bidirectional"))
    )
    (net (code "65") (name "unconnected-(U2-PadADC)") (class "Default")
      (node (ref "U2") (pin "ADC") (pinfunction "ADC_ADC") (pintype "bidirectional"))
    )
    (net (code "66") (name "unconnected-(U2-PadCS0)") (class "Default")
      (node (ref "U2") (pin "CS0") (pinfunction "CS0_CS0") (pintype "bidirectional"))
    )
    (net (code "67") (name "unconnected-(U2-PadGPIO4)") (class "Default")
      (node (ref "U2") (pin "GPIO4") (pinfunction "GPIO4_GPIO4") (pintype "bidirectional"))
    )
    (net (code "68") (name "unconnected-(U2-PadGPIO5)") (class "Default")
      (node (ref "U2") (pin "GPIO5") (pinfunction "GPIO5_GPIO5") (pintype "bidirectional"))
    )
    (net (code "69") (name "unconnected-(U2-PadGPIO12)") (class "Default")
      (node (ref "U2") (pin "GPIO12") (pinfunction "GPIO12_GPIO12") (pintype "bidirectional"))
    )
    (net (code "70") (name "unconnected-(U2-PadGPIO13)") (class "Default")
      (node (ref "U2") (pin "GPIO13") (pinfunction "GPIO13_GPIO13") (pintype "bidirectional"))
    )
    (net (code "71") (name "unconnected-(U2-PadGPIO14)") (class "Default")
      (node (ref "U2") (pin "GPIO14") (pinfunction "GPIO14_GPIO14") (pintype "bidirectional"))
    )
    (net (code "72") (name "unconnected-(U2-PadGPIO15)") (class "Default")
      (node (ref "U2") (pin "GPIO15") (pinfunction "GPIO15_GPIO15") (pintype "bidirectional"))
    )
    (net (code "73") (name "unconnected-(U2-PadGPIO16)") (class "Default")
      (node (ref "U2") (pin "GPIO16") (pinfunction "GPIO16_GPIO16") (pintype "bidirectional"))
    )
    (net (code "74") (name "unconnected-(U2-PadMISO)") (class "Default")
      (node (ref "U2") (pin "MISO") (pinfunction "MISO_MISO") (pintype "bidirectional"))
    )
    (net (code "75") (name "unconnected-(U2-PadMOSI)") (class "Default")
      (node (ref "U2") (pin "MOSI") (pinfunction "MOSI_MOSI") (pintype "bidirectional"))
    )
    (net (code "76") (name "unconnected-(U2-PadSCLK)") (class "Default")
      (node (ref "U2") (pin "SCLK") (pinfunction "SCLK_SCLK") (pintype "bidirectional"))
    )
  )
)
